# usb-shock-buzzer.net
KiCad netlist of a schematic drawn in EAGLE
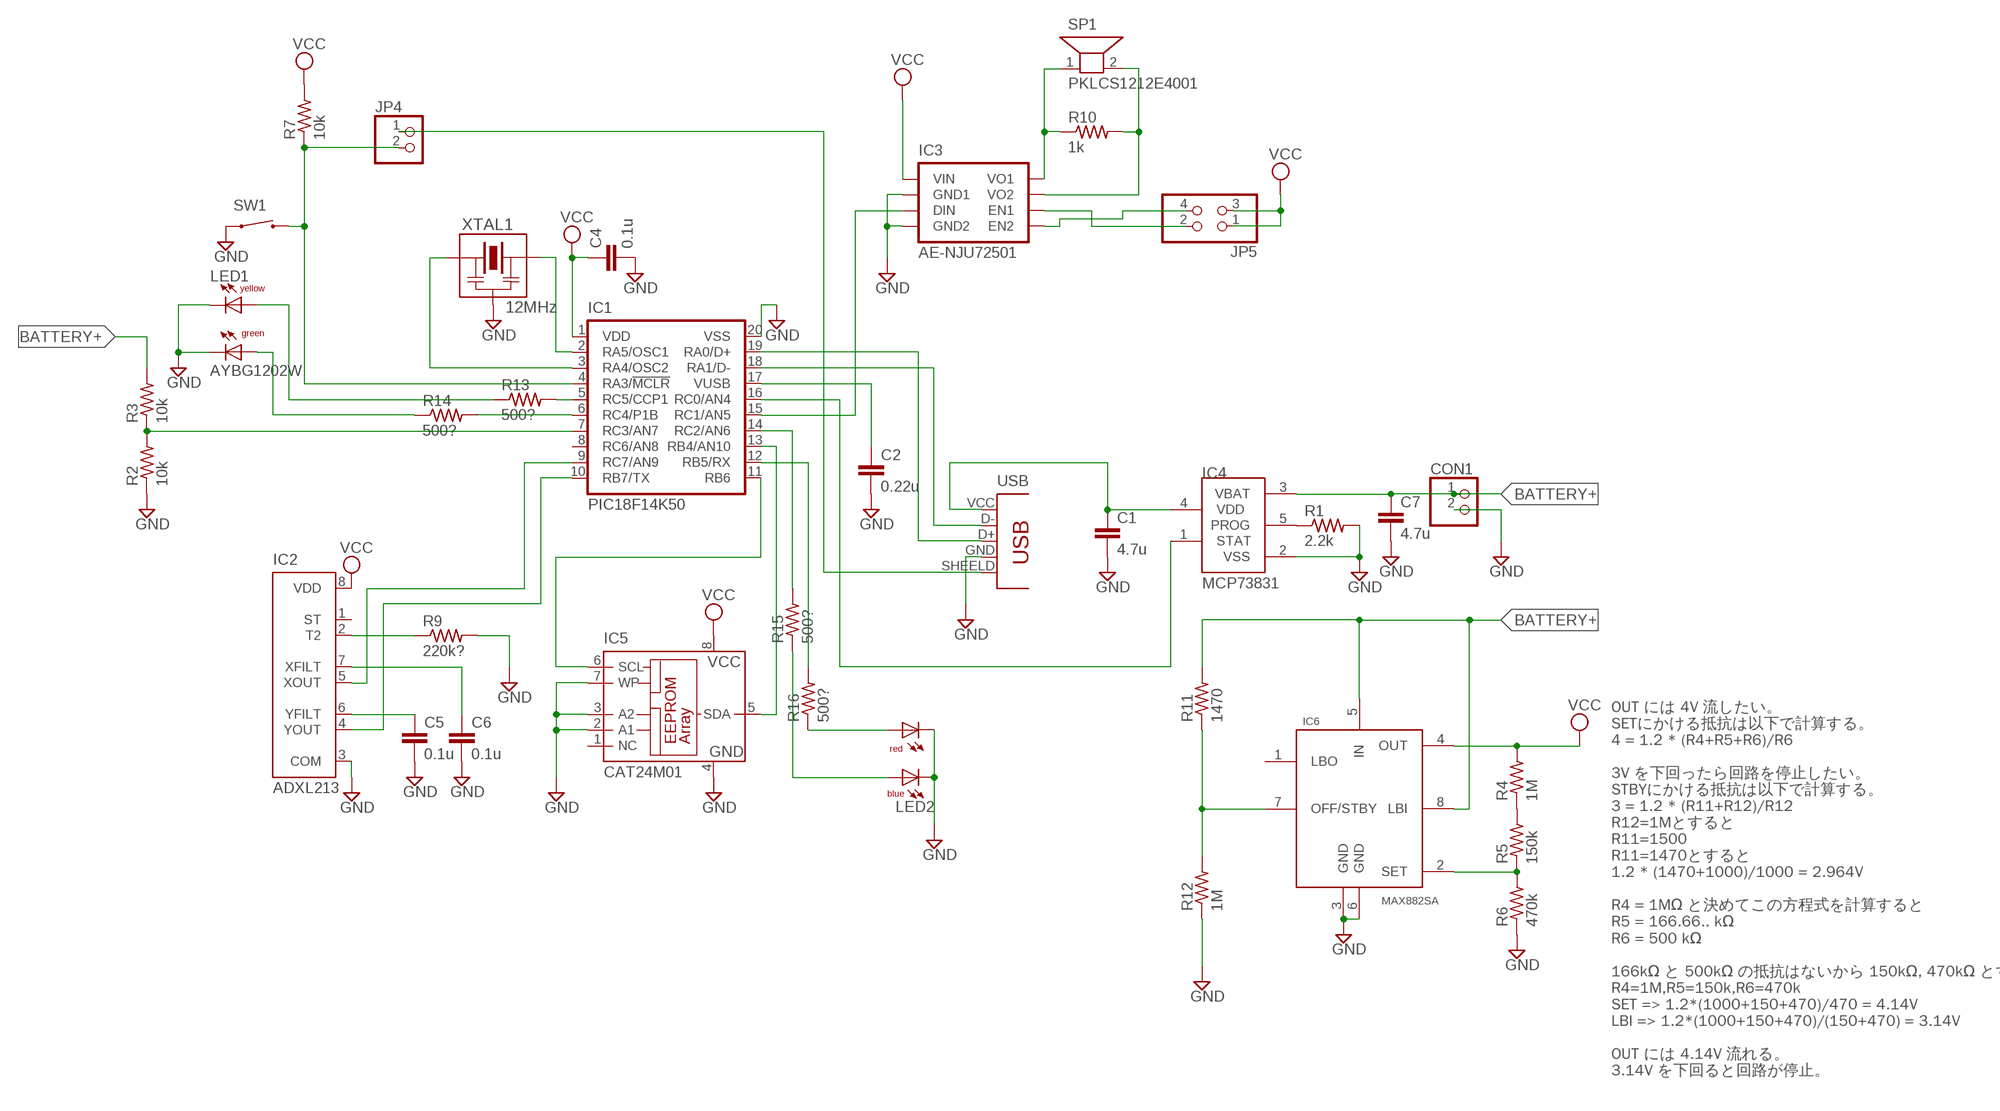
[diagram p0: schematic, sheet 1]

(export (version "E")
  (design (tool "Eeschema 10.0.6"))
  (components
    (comp (ref "C1")
      (value "4.7u")
      (footprint "eagle-import:C0805")
      (libsource (lib "eagle-import") (part "C-EUC0805"))
    )
    (comp (ref "C2")
      (value "0.22u")
      (footprint "eagle-import:C0805")
      (libsource (lib "eagle-import") (part "C-EUC0805"))
    )
    (comp (ref "C4")
      (value "0.1u")
      (footprint "eagle-import:C0805")
      (libsource (lib "eagle-import") (part "C-EUC0805"))
    )
    (comp (ref "C5")
      (value "0.1u")
      (footprint "eagle-import:C0805")
      (libsource (lib "eagle-import") (part "C-EUC0805"))
    )
    (comp (ref "C6")
      (value "0.1u")
      (footprint "eagle-import:C0805")
      (libsource (lib "eagle-import") (part "C-EUC0805"))
    )
    (comp (ref "C7")
      (value "4.7u")
      (footprint "eagle-import:C0805")
      (libsource (lib "eagle-import") (part "C-EUC0805"))
    )
    (comp (ref "CON1")
      (value "PH-2PIN")
      (footprint "eagle-import:PH-2PIN")
      (libsource (lib "eagle-import") (part "PH-2PIN"))
    )
    (comp (ref "IC1")
      (value "PIC18F14K50")
      (footprint "eagle-import:SO20")
      (libsource (lib "eagle-import") (part "PIC18F14K50"))
    )
    (comp (ref "IC2")
      (value "ADXL213")
      (footprint "eagle-import:LCC8")
      (libsource (lib "eagle-import") (part "ADXL213"))
    )
    (comp (ref "IC3")
      (value "AE-NJU72501")
      (footprint "eagle-import:AE-NJU72501")
      (libsource (lib "eagle-import") (part "AE-NJU72501"))
    )
    (comp (ref "IC4")
      (value "MCP73831")
      (footprint "eagle-import:SOT23-5L")
      (libsource (lib "eagle-import") (part "MCP73831"))
    )
    (comp (ref "IC5")
      (value "CAT24M01")
      (footprint "eagle-import:SOIC")
      (libsource (lib "eagle-import") (part "CAT24M01"))
    )
    (comp (ref "IC6")
      (value "MAX882SA")
      (footprint "eagle-import:8-SO")
      (libsource (lib "eagle-import") (part "MAX882SA"))
    )
    (comp (ref "JP4")
      (value "PINHD-1X2")
      (footprint "eagle-import:1X02")
      (libsource (lib "eagle-import") (part "PINHD-1X2"))
    )
    (comp (ref "JP5")
      (value "PINHD-2X2")
      (footprint "eagle-import:2X02")
      (libsource (lib "eagle-import") (part "PINHD-2X2"))
    )
    (comp (ref "LED1")
      (value "AYBG1202W")
      (footprint "eagle-import:AYBG1202W")
      (libsource (lib "eagle-import") (part "AYBG1202W"))
    )
    (comp (ref "LED2")
      (value "2COLOR-BR")
      (footprint "eagle-import:SML-02")
      (libsource (lib "eagle-import") (part "2COLOR-BR"))
    )
    (comp (ref "R1")
      (value "2.2k")
      (footprint "eagle-import:M0805")
      (libsource (lib "eagle-import") (part "R-US_M0805"))
    )
    (comp (ref "R2")
      (value "10k")
      (footprint "eagle-import:M0805")
      (libsource (lib "eagle-import") (part "R-US_M0805"))
    )
    (comp (ref "R3")
      (value "10k")
      (footprint "eagle-import:M0805")
      (libsource (lib "eagle-import") (part "R-US_M0805"))
    )
    (comp (ref "R4")
      (value "1M")
      (footprint "eagle-import:R0805")
      (libsource (lib "eagle-import") (part "R-US_R0805"))
    )
    (comp (ref "R5")
      (value "150k")
      (footprint "eagle-import:M0805")
      (libsource (lib "eagle-import") (part "R-US_M0805"))
    )
    (comp (ref "R6")
      (value "470k")
      (footprint "eagle-import:M0805")
      (libsource (lib "eagle-import") (part "R-US_M0805"))
    )
    (comp (ref "R7")
      (value "10k")
      (footprint "eagle-import:M0805")
      (libsource (lib "eagle-import") (part "R-US_M0805"))
    )
    (comp (ref "R9")
      (value "220k?")
      (footprint "eagle-import:M0805")
      (libsource (lib "eagle-import") (part "R-US_M0805"))
    )
    (comp (ref "R10")
      (value "1k")
      (footprint "eagle-import:M1206")
      (libsource (lib "eagle-import") (part "R-US_M1206"))
    )
    (comp (ref "R11")
      (value "1470")
      (footprint "eagle-import:R0805")
      (libsource (lib "eagle-import") (part "R-US_R0805"))
    )
    (comp (ref "R12")
      (value "1M")
      (footprint "eagle-import:R0805")
      (libsource (lib "eagle-import") (part "R-US_R0805"))
    )
    (comp (ref "R13")
      (value "500?")
      (footprint "eagle-import:M0805")
      (libsource (lib "eagle-import") (part "R-US_M0805"))
    )
    (comp (ref "R14")
      (value "500?")
      (footprint "eagle-import:M0805")
      (libsource (lib "eagle-import") (part "R-US_M0805"))
    )
    (comp (ref "R15")
      (value "500?")
      (footprint "eagle-import:M0805")
      (libsource (lib "eagle-import") (part "R-US_M0805"))
    )
    (comp (ref "R16")
      (value "500?")
      (footprint "eagle-import:M0805")
      (libsource (lib "eagle-import") (part "R-US_M0805"))
    )
    (comp (ref "SP1")
      (value "PKLCS1212E4001")
      (footprint "eagle-import:PKLCS1212E4001")
      (libsource (lib "eagle-import") (part "PKLCS1212E4001"))
    )
    (comp (ref "SW1")
      (value "TVBP06")
      (footprint "eagle-import:TVBP06")
      (libsource (lib "eagle-import") (part "TVBP06"))
    )
    (comp (ref "USB")
      (value "TYPE-A+SHILED")
      (footprint "eagle-import:TYPE-A")
      (libsource (lib "eagle-import") (part "TYPE-A+SHILED"))
    )
    (comp (ref "XTAL1")
      (value "12MHz")
      (footprint "eagle-import:CSTCE")
      (libsource (lib "eagle-import") (part "CSTCE12M0G15L"))
    )
  )
  (nets
    (net (code "1") (name "BATTERY+") (class "Default")
      (node (ref "C7") (pin "1") (pinfunction "1_1") (pintype "passive"))
      (node (ref "CON1") (pin "1") (pinfunction "1_1") (pintype "passive"))
      (node (ref "IC4") (pin "3") (pinfunction "VBAT_3") (pintype "bidirectional"))
      (node (ref "IC6") (pin "5") (pinfunction "IN_5") (pintype "power_in"))
      (node (ref "IC6") (pin "8") (pinfunction "LBI_8") (pintype "passive"))
      (node (ref "R11") (pin "2") (pinfunction "2_2") (pintype "passive"))
      (node (ref "R3") (pin "2") (pinfunction "2_2") (pintype "passive"))
    )
    (net (code "2") (name "GND") (class "Default")
      (node (ref "C1") (pin "2") (pinfunction "2_2") (pintype "passive"))
      (node (ref "C2") (pin "2") (pinfunction "2_2") (pintype "passive"))
      (node (ref "C4") (pin "2") (pinfunction "2_2") (pintype "passive"))
      (node (ref "C5") (pin "2") (pinfunction "2_2") (pintype "passive"))
      (node (ref "C6") (pin "2") (pinfunction "2_2") (pintype "passive"))
      (node (ref "C7") (pin "2") (pinfunction "2_2") (pintype "passive"))
      (node (ref "CON1") (pin "2") (pinfunction "2_2") (pintype "passive"))
      (node (ref "IC1") (pin "20") (pinfunction "VSS_20") (pintype "power_in"))
      (node (ref "IC2") (pin "3") (pinfunction "COM_3") (pintype "input"))
      (node (ref "IC3") (pin "2") (pinfunction "GND1_2") (pintype "power_in"))
      (node (ref "IC3") (pin "4") (pinfunction "GND2_4") (pintype "power_in"))
      (node (ref "IC4") (pin "2") (pinfunction "VSS_2") (pintype "bidirectional"))
      (node (ref "IC5") (pin "2") (pinfunction "A1_2") (pintype "input"))
      (node (ref "IC5") (pin "3") (pinfunction "A2_3") (pintype "input"))
      (node (ref "IC5") (pin "4") (pinfunction "GND_4") (pintype "power_in"))
      (node (ref "IC5") (pin "7") (pinfunction "WP_7") (pintype "input"))
      (node (ref "IC6") (pin "3") (pinfunction "GND_3") (pintype "power_in"))
      (node (ref "IC6") (pin "6") (pinfunction "GND_6") (pintype "power_in"))
      (node (ref "LED1") (pin "2") (pinfunction "CC1_2") (pintype "passive"))
      (node (ref "LED1") (pin "4") (pinfunction "CC2_4") (pintype "passive"))
      (node (ref "LED2") (pin "1") (pinfunction "CC1_1") (pintype "passive"))
      (node (ref "LED2") (pin "3") (pinfunction "CC2_3") (pintype "passive"))
      (node (ref "R1") (pin "2") (pinfunction "2_2") (pintype "passive"))
      (node (ref "R12") (pin "1") (pinfunction "1_1") (pintype "passive"))
      (node (ref "R2") (pin "1") (pinfunction "1_1") (pintype "passive"))
      (node (ref "R6") (pin "1") (pinfunction "1_1") (pintype "passive"))
      (node (ref "R9") (pin "2") (pinfunction "2_2") (pintype "passive"))
      (node (ref "SW1") (pin "1") (pinfunction "1_1") (pintype "passive"))
      (node (ref "USB") (pin "GND") (pinfunction "4_GND") (pintype "power_in"))
      (node (ref "XTAL1") (pin "2") (pinfunction "GND_2") (pintype "bidirectional"))
    )
    (net (code "3") (name "Net-(IC1-RA0{slash}D+)") (class "Default")
      (node (ref "IC1") (pin "19") (pinfunction "RA0/D+_19") (pintype "bidirectional"))
      (node (ref "USB") (pin "D+") (pinfunction "3_D+") (pintype "passive"))
    )
    (net (code "4") (name "Net-(IC1-RA1{slash}D-)") (class "Default")
      (node (ref "IC1") (pin "18") (pinfunction "RA1/D-_18") (pintype "bidirectional"))
      (node (ref "USB") (pin "D-") (pinfunction "2_D-") (pintype "passive"))
    )
    (net (code "5") (name "Net-(IC1-RA3{slash}~{MCLR})") (class "Default")
      (node (ref "IC1") (pin "4") (pinfunction "RA3/~{MCLR}_4") (pintype "bidirectional"))
      (node (ref "JP4") (pin "2") (pinfunction "2_2") (pintype "passive"))
      (node (ref "R7") (pin "1") (pinfunction "1_1") (pintype "passive"))
      (node (ref "SW1") (pin "2") (pinfunction "2_2") (pintype "passive"))
    )
    (net (code "6") (name "Net-(IC1-RA4{slash}OSC2)") (class "Default")
      (node (ref "IC1") (pin "3") (pinfunction "RA4/OSC2_3") (pintype "bidirectional"))
      (node (ref "XTAL1") (pin "1") (pinfunction "LFT_1") (pintype "bidirectional"))
    )
    (net (code "7") (name "Net-(IC1-RA5{slash}OSC1)") (class "Default")
      (node (ref "IC1") (pin "2") (pinfunction "RA5/OSC1_2") (pintype "bidirectional"))
      (node (ref "XTAL1") (pin "3") (pinfunction "RIT_3") (pintype "bidirectional"))
    )
    (net (code "8") (name "Net-(IC1-RB4{slash}AN10)") (class "Default")
      (node (ref "IC1") (pin "13") (pinfunction "RB4/AN10_13") (pintype "bidirectional"))
      (node (ref "IC5") (pin "5") (pinfunction "SDA_5") (pintype "bidirectional"))
    )
    (net (code "9") (name "Net-(IC1-RB5{slash}RX)") (class "Default")
      (node (ref "IC1") (pin "12") (pinfunction "RB5/RX_12") (pintype "bidirectional"))
      (node (ref "R16") (pin "2") (pinfunction "2_2") (pintype "passive"))
    )
    (net (code "10") (name "Net-(IC1-RB6)") (class "Default")
      (node (ref "IC1") (pin "11") (pinfunction "RB6_11") (pintype "bidirectional"))
      (node (ref "IC5") (pin "6") (pinfunction "SCL_6") (pintype "input"))
    )
    (net (code "11") (name "Net-(IC1-RB7{slash}TX)") (class "Default")
      (node (ref "IC1") (pin "10") (pinfunction "RB7/TX_10") (pintype "bidirectional"))
      (node (ref "IC2") (pin "4") (pinfunction "YOUT_4") (pintype "input"))
    )
    (net (code "12") (name "Net-(IC1-RC0{slash}AN4)") (class "Default")
      (node (ref "IC1") (pin "16") (pinfunction "RC0/AN4_16") (pintype "bidirectional"))
      (node (ref "IC4") (pin "1") (pinfunction "STAT_1") (pintype "bidirectional"))
    )
    (net (code "13") (name "Net-(IC1-RC1{slash}AN5)") (class "Default")
      (node (ref "IC1") (pin "15") (pinfunction "RC1/AN5_15") (pintype "bidirectional"))
      (node (ref "IC3") (pin "3") (pinfunction "DIN_3") (pintype "bidirectional"))
    )
    (net (code "14") (name "Net-(IC1-RC2{slash}AN6)") (class "Default")
      (node (ref "IC1") (pin "14") (pinfunction "RC2/AN6_14") (pintype "bidirectional"))
      (node (ref "R15") (pin "2") (pinfunction "2_2") (pintype "passive"))
    )
    (net (code "15") (name "Net-(IC1-RC3{slash}AN7)") (class "Default")
      (node (ref "IC1") (pin "7") (pinfunction "RC3/AN7_7") (pintype "bidirectional"))
      (node (ref "R2") (pin "2") (pinfunction "2_2") (pintype "passive"))
      (node (ref "R3") (pin "1") (pinfunction "1_1") (pintype "passive"))
    )
    (net (code "16") (name "Net-(IC1-RC4{slash}P1B)") (class "Default")
      (node (ref "IC1") (pin "6") (pinfunction "RC4/P1B_6") (pintype "bidirectional"))
      (node (ref "R14") (pin "2") (pinfunction "2_2") (pintype "passive"))
    )
    (net (code "17") (name "Net-(IC1-RC5{slash}CCP1)") (class "Default")
      (node (ref "IC1") (pin "5") (pinfunction "RC5/CCP1_5") (pintype "bidirectional"))
      (node (ref "R13") (pin "2") (pinfunction "2_2") (pintype "passive"))
    )
    (net (code "18") (name "Net-(IC1-RC7{slash}AN9)") (class "Default")
      (node (ref "IC1") (pin "9") (pinfunction "RC7/AN9_9") (pintype "bidirectional"))
      (node (ref "IC2") (pin "5") (pinfunction "XOUT_5") (pintype "input"))
    )
    (net (code "19") (name "Net-(IC1-VUSB)") (class "Default")
      (node (ref "C2") (pin "1") (pinfunction "1_1") (pintype "passive"))
      (node (ref "IC1") (pin "17") (pinfunction "VUSB_17") (pintype "bidirectional"))
    )
    (net (code "20") (name "Net-(IC2-T2)") (class "Default")
      (node (ref "IC2") (pin "2") (pinfunction "T2_2") (pintype "input"))
      (node (ref "R9") (pin "1") (pinfunction "1_1") (pintype "passive"))
    )
    (net (code "21") (name "Net-(IC2-XFILT)") (class "Default")
      (node (ref "C6") (pin "1") (pinfunction "1_1") (pintype "passive"))
      (node (ref "IC2") (pin "7") (pinfunction "XFILT_7") (pintype "input"))
    )
    (net (code "22") (name "Net-(IC2-YFILT)") (class "Default")
      (node (ref "C5") (pin "1") (pinfunction "1_1") (pintype "passive"))
      (node (ref "IC2") (pin "6") (pinfunction "YFILT_6") (pintype "input"))
    )
    (net (code "23") (name "Net-(IC3-EN1)") (class "Default")
      (node (ref "IC3") (pin "6") (pinfunction "EN1_6") (pintype "bidirectional"))
      (node (ref "JP5") (pin "2") (pinfunction "2_2") (pintype "passive"))
    )
    (net (code "24") (name "Net-(IC3-EN2)") (class "Default")
      (node (ref "IC3") (pin "5") (pinfunction "EN2_5") (pintype "power_in"))
      (node (ref "JP5") (pin "4") (pinfunction "4_4") (pintype "passive"))
    )
    (net (code "25") (name "Net-(IC3-VO1)") (class "Default")
      (node (ref "IC3") (pin "8") (pinfunction "VO1_8") (pintype "bidirectional"))
      (node (ref "R10") (pin "1") (pinfunction "1_1") (pintype "passive"))
      (node (ref "SP1") (pin "1") (pinfunction "1_1") (pintype "passive"))
    )
    (net (code "26") (name "Net-(IC3-VO2)") (class "Default")
      (node (ref "IC3") (pin "7") (pinfunction "VO2_7") (pintype "bidirectional"))
      (node (ref "R10") (pin "2") (pinfunction "2_2") (pintype "passive"))
      (node (ref "SP1") (pin "2") (pinfunction "2_2") (pintype "passive"))
    )
    (net (code "27") (name "Net-(IC4-PROG)") (class "Default")
      (node (ref "IC4") (pin "5") (pinfunction "PROG_5") (pintype "bidirectional"))
      (node (ref "R1") (pin "1") (pinfunction "1_1") (pintype "passive"))
    )
    (net (code "28") (name "Net-(IC4-VDD)") (class "Default")
      (node (ref "C1") (pin "1") (pinfunction "1_1") (pintype "passive"))
      (node (ref "IC4") (pin "4") (pinfunction "VDD_4") (pintype "bidirectional"))
      (node (ref "USB") (pin "VCC") (pinfunction "1_VCC") (pintype "power_in"))
    )
    (net (code "29") (name "Net-(IC6-OFF{slash}STBY)") (class "Default")
      (node (ref "IC6") (pin "7") (pinfunction "OFF/STBY_7") (pintype "passive"))
      (node (ref "R11") (pin "1") (pinfunction "1_1") (pintype "passive"))
      (node (ref "R12") (pin "2") (pinfunction "2_2") (pintype "passive"))
    )
    (net (code "30") (name "Net-(IC6-SET)") (class "Default")
      (node (ref "IC6") (pin "2") (pinfunction "SET_2") (pintype "passive"))
      (node (ref "R5") (pin "1") (pinfunction "1_1") (pintype "passive"))
      (node (ref "R6") (pin "2") (pinfunction "2_2") (pintype "passive"))
    )
    (net (code "31") (name "Net-(LED1-A1)") (class "Default")
      (node (ref "LED1") (pin "1") (pinfunction "A1_1") (pintype "passive"))
      (node (ref "R13") (pin "1") (pinfunction "1_1") (pintype "passive"))
    )
    (net (code "32") (name "Net-(LED1-A2)") (class "Default")
      (node (ref "LED1") (pin "3") (pinfunction "A2_3") (pintype "passive"))
      (node (ref "R14") (pin "1") (pinfunction "1_1") (pintype "passive"))
    )
    (net (code "33") (name "Net-(LED2-AB)") (class "Default")
      (node (ref "LED2") (pin "2") (pinfunction "AB_2") (pintype "passive"))
      (node (ref "R15") (pin "1") (pinfunction "1_1") (pintype "passive"))
    )
    (net (code "34") (name "Net-(LED2-AR)") (class "Default")
      (node (ref "LED2") (pin "4") (pinfunction "AR_4") (pintype "passive"))
      (node (ref "R16") (pin "1") (pinfunction "1_1") (pintype "passive"))
    )
    (net (code "35") (name "Net-(R4-Pad1)") (class "Default")
      (node (ref "R4") (pin "1") (pinfunction "1_1") (pintype "passive"))
      (node (ref "R5") (pin "2") (pinfunction "2_2") (pintype "passive"))
    )
    (net (code "36") (name "Net-(USB-5)") (class "Default")
      (node (ref "JP4") (pin "1") (pinfunction "1_1") (pintype "passive"))
      (node (ref "USB") (pin "SHEELD") (pinfunction "5_SHEELD") (pintype "passive"))
    )
    (net (code "37") (name "VCC") (class "Default")
      (node (ref "C4") (pin "1") (pinfunction "1_1") (pintype "passive"))
      (node (ref "IC1") (pin "1") (pinfunction "VDD_1") (pintype "power_in"))
      (node (ref "IC2") (pin "8") (pinfunction "VDD_8") (pintype "input"))
      (node (ref "IC3") (pin "1") (pinfunction "VIN_1") (pintype "power_in"))
      (node (ref "IC5") (pin "8") (pinfunction "VCC_8") (pintype "power_in"))
      (node (ref "IC6") (pin "4") (pinfunction "OUT_4") (pintype "power_in"))
      (node (ref "JP5") (pin "1") (pinfunction "1_1") (pintype "passive"))
      (node (ref "JP5") (pin "3") (pinfunction "3_3") (pintype "passive"))
      (node (ref "R4") (pin "2") (pinfunction "2_2") (pintype "passive"))
      (node (ref "R7") (pin "2") (pinfunction "2_2") (pintype "passive"))
    )
    (net (code "38") (name "unconnected-(IC1-RC6{slash}AN8-Pad8)") (class "Default")
      (node (ref "IC1") (pin "8") (pinfunction "RC6/AN8_8") (pintype "bidirectional"))
    )
    (net (code "39") (name "unconnected-(IC2-ST-Pad1)") (class "Default")
      (node (ref "IC2") (pin "1") (pinfunction "ST_1") (pintype "input"))
    )
    (net (code "40") (name "unconnected-(IC5-NC-Pad1)") (class "Default")
      (node (ref "IC5") (pin "1") (pinfunction "NC_1") (pintype "input"))
    )
    (net (code "41") (name "unconnected-(IC6-LBO-Pad1)") (class "Default")
      (node (ref "IC6") (pin "1") (pinfunction "LBO_1") (pintype "open_collector"))
    )
  )
)
